# magnetophone.net
KiCad netlist of a schematic drawn in EAGLE
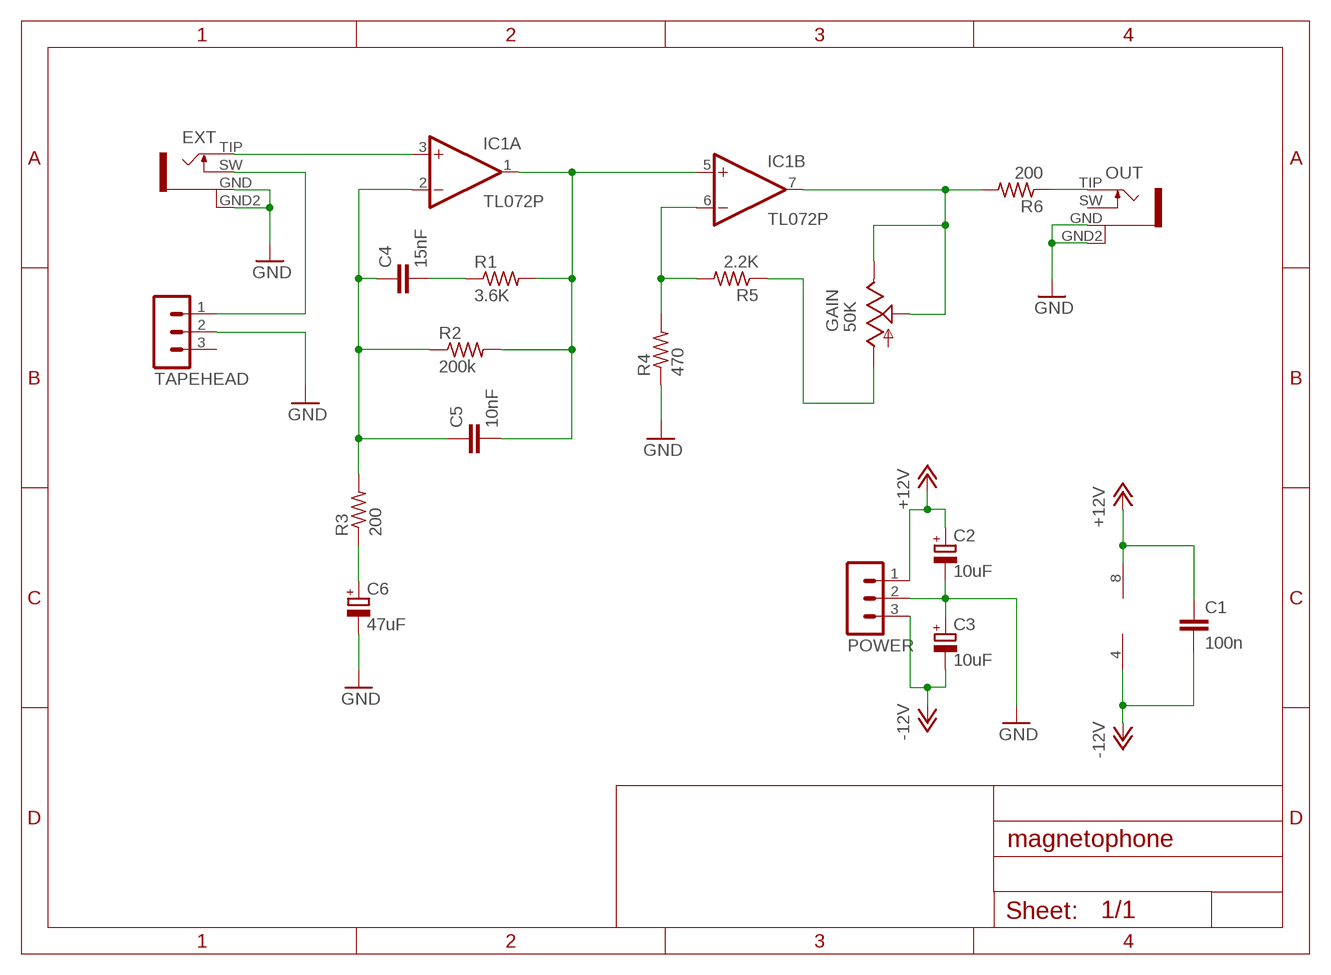
[diagram p0: schematic, sheet 1]

(export (version "E")
  (design (tool "Eeschema 10.0.6"))
  (components
    (comp (ref "C1")
      (value "100n")
      (footprint "eagle-import:C025-025X050")
      (libsource (lib "eagle-import") (part "C-EU025-025X050"))
    )
    (comp (ref "C2")
      (value "10uF")
      (footprint "eagle-import:E2,5-6E")
      (libsource (lib "eagle-import") (part "CPOL-EUE2,5-6E"))
    )
    (comp (ref "C3")
      (value "10uF")
      (footprint "eagle-import:E2,5-6E")
      (libsource (lib "eagle-import") (part "CPOL-EUE2,5-6E"))
    )
    (comp (ref "C4")
      (value "15nF")
      (footprint "eagle-import:C025-025X050")
      (libsource (lib "eagle-import") (part "C-EU025-025X050"))
    )
    (comp (ref "C5")
      (value "10nF")
      (footprint "eagle-import:C025-025X050")
      (libsource (lib "eagle-import") (part "C-EU025-025X050"))
    )
    (comp (ref "C6")
      (value "47uF")
      (footprint "eagle-import:E2,5-6E")
      (libsource (lib "eagle-import") (part "CPOL-EUE2,5-6E"))
    )
    (comp (ref "EXT")
      (value "PJ301BM")
      (footprint "eagle-import:PJ301")
      (libsource (lib "eagle-import") (part "PJ301BM"))
    )
    (comp (ref "GAIN")
      (value "50K")
      (footprint "eagle-import:9MM_SNAP-IN_POT")
      (libsource (lib "eagle-import") (part "9MM_SNAP-IN_POT_"))
    )
    (comp (ref "IC1")
      (value "TL072P")
      (footprint "eagle-import:DIL08")
      (libsource (lib "eagle-import") (part "TL072P"))
    )
    (comp (ref "OUT")
      (value "PJ301BM")
      (footprint "eagle-import:PJ301")
      (libsource (lib "eagle-import") (part "PJ301BM"))
    )
    (comp (ref "POWER")
      (value "MA03-1")
      (footprint "eagle-import:MA03-1")
      (libsource (lib "eagle-import") (part "MA03-1"))
    )
    (comp (ref "R1")
      (value "3.6K")
      (footprint "eagle-import:0207_10")
      (libsource (lib "eagle-import") (part "R-US_0207/10"))
    )
    (comp (ref "R2")
      (value "200k")
      (footprint "eagle-import:0207_10")
      (libsource (lib "eagle-import") (part "R-US_0207/10"))
    )
    (comp (ref "R3")
      (value "200")
      (footprint "eagle-import:0207_10")
      (libsource (lib "eagle-import") (part "R-US_0207/10"))
    )
    (comp (ref "R4")
      (value "470")
      (footprint "eagle-import:0207_10")
      (libsource (lib "eagle-import") (part "R-US_0207/10"))
    )
    (comp (ref "R5")
      (value "2.2K")
      (footprint "eagle-import:0207_10")
      (libsource (lib "eagle-import") (part "R-US_0207/10"))
    )
    (comp (ref "R6")
      (value "200")
      (footprint "eagle-import:0207_10")
      (libsource (lib "eagle-import") (part "R-US_0207/10"))
    )
    (comp (ref "TAPEHEAD")
      (value "MA03-1")
      (footprint "eagle-import:MA03-1")
      (libsource (lib "eagle-import") (part "MA03-1"))
    )
  )
  (nets
    (net (code "1") (name "+12V") (class "Default")
      (node (ref "C1") (pin "1") (pinfunction "1_1") (pintype "passive"))
      (node (ref "C2") (pin "+") (pinfunction "+_+") (pintype "passive"))
      (node (ref "IC1") (pin "8") (pinfunction "V+_8") (pintype "power_in"))
      (node (ref "POWER") (pin "1") (pinfunction "1_1") (pintype "passive"))
    )
    (net (code "2") (name "-12V") (class "Default")
      (node (ref "C1") (pin "2") (pinfunction "2_2") (pintype "passive"))
      (node (ref "C3") (pin "-") (pinfunction "-_-") (pintype "passive"))
      (node (ref "IC1") (pin "4") (pinfunction "V-_4") (pintype "power_in"))
      (node (ref "POWER") (pin "3") (pinfunction "3_3") (pintype "passive"))
    )
    (net (code "3") (name "GND") (class "Default")
      (node (ref "C2") (pin "-") (pinfunction "-_-") (pintype "passive"))
      (node (ref "C3") (pin "+") (pinfunction "+_+") (pintype "passive"))
      (node (ref "C6") (pin "-") (pinfunction "-_-") (pintype "passive"))
      (node (ref "EXT") (pin "GND") (pinfunction "1_GND") (pintype "passive"))
      (node (ref "EXT") (pin "GND2") (pinfunction "4_GND2") (pintype "passive"))
      (node (ref "OUT") (pin "GND") (pinfunction "1_GND") (pintype "passive"))
      (node (ref "OUT") (pin "GND2") (pinfunction "4_GND2") (pintype "passive"))
      (node (ref "POWER") (pin "2") (pinfunction "2_2") (pintype "passive"))
      (node (ref "R4") (pin "1") (pinfunction "1_1") (pintype "passive"))
      (node (ref "TAPEHEAD") (pin "2") (pinfunction "2_2") (pintype "passive"))
    )
    (net (code "4") (name "Net-(C4-Pad2)") (class "Default")
      (node (ref "C4") (pin "2") (pinfunction "2_2") (pintype "passive"))
      (node (ref "R1") (pin "1") (pinfunction "1_1") (pintype "passive"))
    )
    (net (code "5") (name "Net-(C6-Pad+)") (class "Default")
      (node (ref "C6") (pin "+") (pinfunction "+_+") (pintype "passive"))
      (node (ref "R3") (pin "1") (pinfunction "1_1") (pintype "passive"))
    )
    (net (code "6") (name "Net-(EXT-2)") (class "Default")
      (node (ref "EXT") (pin "TIP") (pinfunction "2_TIP") (pintype "passive"))
      (node (ref "IC1") (pin "3") (pinfunction "+IN_3") (pintype "input"))
    )
    (net (code "7") (name "Net-(EXT-3)") (class "Default")
      (node (ref "EXT") (pin "SW") (pinfunction "3_SW") (pintype "passive"))
      (node (ref "TAPEHEAD") (pin "1") (pinfunction "1_1") (pintype "passive"))
    )
    (net (code "8") (name "Net-(GAIN-A)") (class "Default")
      (node (ref "GAIN") (pin "1") (pinfunction "A_1") (pintype "passive"))
      (node (ref "R5") (pin "1") (pinfunction "1_1") (pintype "passive"))
    )
    (net (code "9") (name "Net-(GAIN-E)") (class "Default")
      (node (ref "GAIN") (pin "2") (pinfunction "S_2") (pintype "passive"))
      (node (ref "GAIN") (pin "3") (pinfunction "E_3") (pintype "passive"))
      (node (ref "IC1") (pin "7") (pinfunction "OUT_7") (pintype "output"))
      (node (ref "R6") (pin "2") (pinfunction "2_2") (pintype "passive"))
    )
    (net (code "10") (name "Net-(IC1A--IN)") (class "Default")
      (node (ref "C4") (pin "1") (pinfunction "1_1") (pintype "passive"))
      (node (ref "C5") (pin "1") (pinfunction "1_1") (pintype "passive"))
      (node (ref "IC1") (pin "2") (pinfunction "-IN_2") (pintype "input"))
      (node (ref "R2") (pin "1") (pinfunction "1_1") (pintype "passive"))
      (node (ref "R3") (pin "2") (pinfunction "2_2") (pintype "passive"))
    )
    (net (code "11") (name "Net-(IC1A-OUT)") (class "Default")
      (node (ref "C5") (pin "2") (pinfunction "2_2") (pintype "passive"))
      (node (ref "IC1") (pin "1") (pinfunction "OUT_1") (pintype "output"))
      (node (ref "IC1") (pin "5") (pinfunction "+IN_5") (pintype "input"))
      (node (ref "R1") (pin "2") (pinfunction "2_2") (pintype "passive"))
      (node (ref "R2") (pin "2") (pinfunction "2_2") (pintype "passive"))
    )
    (net (code "12") (name "Net-(IC1B--IN)") (class "Default")
      (node (ref "IC1") (pin "6") (pinfunction "-IN_6") (pintype "input"))
      (node (ref "R4") (pin "2") (pinfunction "2_2") (pintype "passive"))
      (node (ref "R5") (pin "2") (pinfunction "2_2") (pintype "passive"))
    )
    (net (code "13") (name "Net-(OUT-2)") (class "Default")
      (node (ref "OUT") (pin "TIP") (pinfunction "2_TIP") (pintype "passive"))
      (node (ref "R6") (pin "1") (pinfunction "1_1") (pintype "passive"))
    )
    (net (code "14") (name "unconnected-(OUT-3-PadSW)") (class "Default")
      (node (ref "OUT") (pin "SW") (pinfunction "3_SW") (pintype "passive"))
    )
    (net (code "15") (name "unconnected-(TAPEHEAD-Pad3)") (class "Default")
      (node (ref "TAPEHEAD") (pin "3") (pinfunction "3_3") (pintype "passive"))
    )
  )
)
